# 10_CAN_Bus.net
KiCad netlist of a schematic drawn in Altium Designer
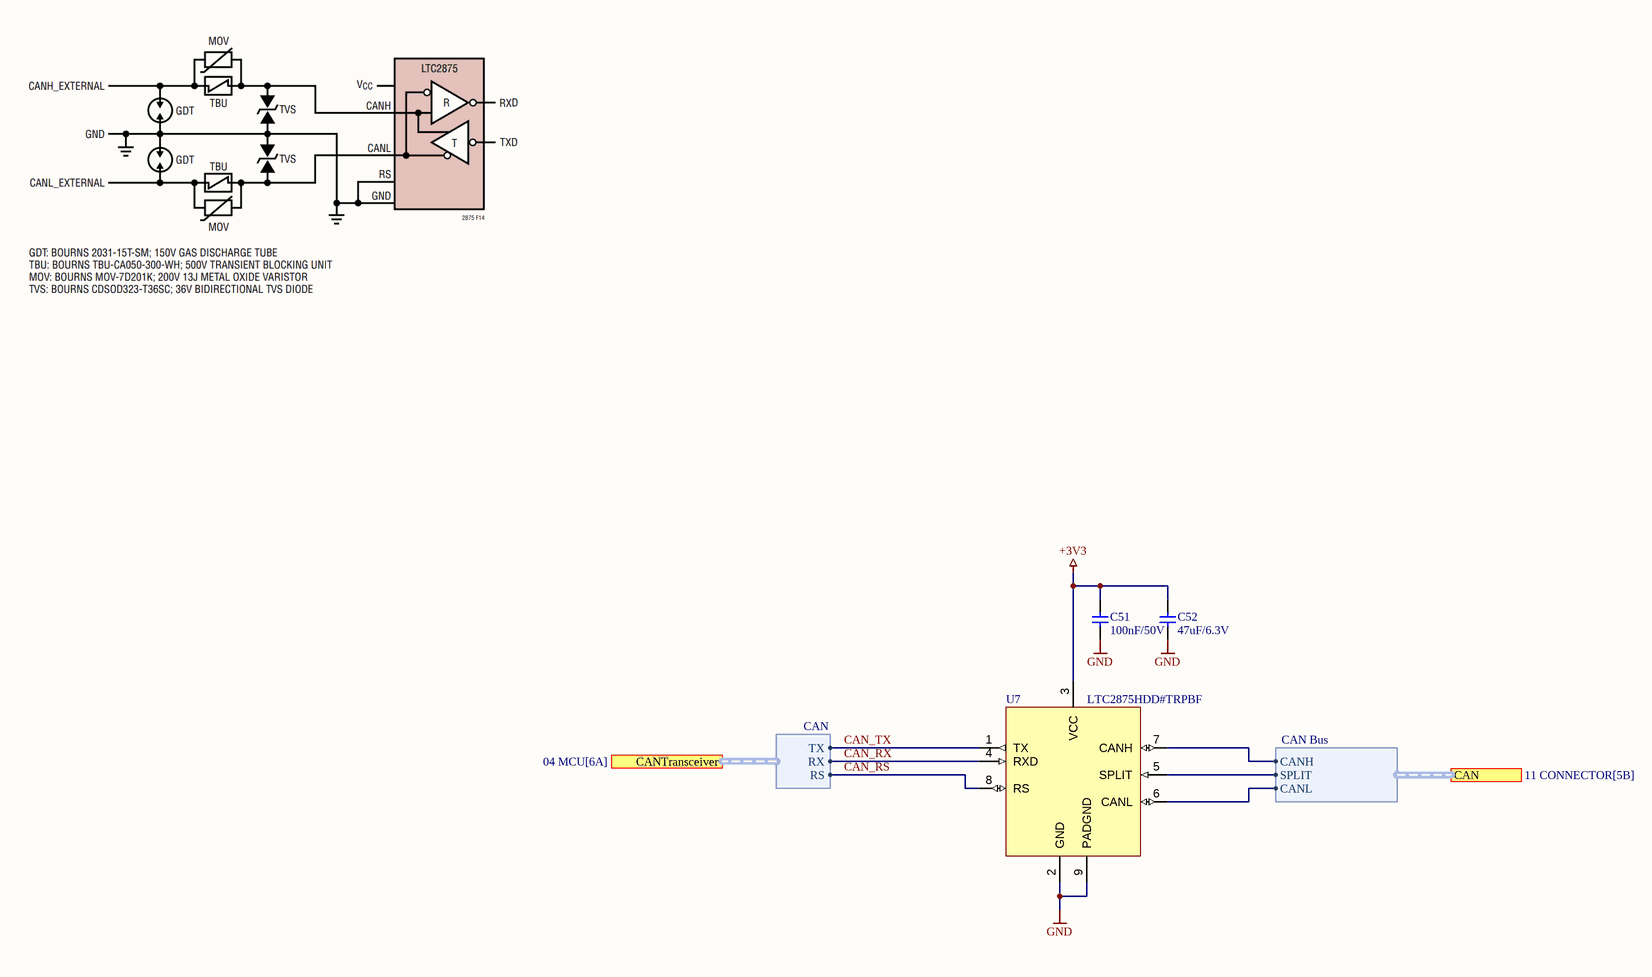
[diagram p0: 10 CAN Bus.SchDoc]

(export (version "E")
  (design (tool "Eeschema 10.0.6"))
  (components
    (comp (ref "C51")
      (value "100nF/50V")
      (footprint "CAPC1005X06M-0402")
      (description "0.1 µF ±10% 50V Ceramic Capacitor X7R 0402 (1005 Metric)")
      (fields (field (name "MPN") "GRM155R71H104KE14D"))
      (libsource (lib "Symbol") (part "GRM155R71H104KE14D"))
    )
    (comp (ref "C52")
      (value "47uF/6.3V")
      (footprint "CAPC1608X10M-0603")
      (description "47 µF ±20% 6.3V Ceramic Capacitor X5R 0603 (1608 Metric)")
      (fields (field (name "MPN") "GRM188R60J476ME15D"))
      (libsource (lib "Symbol") (part "GRM188R60J476ME15D"))
    )
    (comp (ref "U7")
      (value "LTC2875HDD#TRPBF")
      (footprint "DFN-8")
      (description "1/1 Transceiver CANbus 8-DFN (3x3)")
      (libsource (lib "Symbol") (part "LTC2875HDD#TRPBF"))
    )
  )
  (nets
    (net (code "3") (name "+3V3") (class "Default")
      (node (ref "C51") (pin "2") (pinfunction "2_2") (pintype "passive"))
      (node (ref "C52") (pin "2") (pinfunction "2_2") (pintype "passive"))
      (node (ref "U7") (pin "3") (pinfunction "VCC_3") (pintype "power_in"))
    )
    (net (code "4") (name "/CANH") (class "Default")
      (node (ref "U7") (pin "7") (pinfunction "CANH_7") (pintype "bidirectional"))
    )
    (net (code "5") (name "/CANL") (class "Default")
      (node (ref "U7") (pin "6") (pinfunction "CANL_6") (pintype "bidirectional"))
    )
    (net (code "6") (name "/CAN_RS") (class "Default")
      (node (ref "U7") (pin "8") (pinfunction "RS_8") (pintype "bidirectional"))
    )
    (net (code "7") (name "/CAN_RX") (class "Default")
      (node (ref "U7") (pin "4") (pinfunction "RXD_4") (pintype "input"))
    )
    (net (code "8") (name "/CAN_TX") (class "Default")
      (node (ref "U7") (pin "1") (pinfunction "TX_1") (pintype "output"))
    )
    (net (code "9") (name "/SPLIT") (class "Default")
      (node (ref "U7") (pin "5") (pinfunction "SPLIT_5") (pintype "input"))
    )
    (net (code "12") (name "GND") (class "Default")
      (node (ref "C51") (pin "1") (pinfunction "1_1") (pintype "passive"))
      (node (ref "C52") (pin "1") (pinfunction "1_1") (pintype "passive"))
      (node (ref "U7") (pin "2") (pinfunction "GND_2") (pintype "power_in"))
      (node (ref "U7") (pin "9") (pinfunction "PADGND_9") (pintype "power_in"))
    )
  )
)
